# 03_LTC6820.net
KiCad netlist of a schematic drawn in Altium Designer
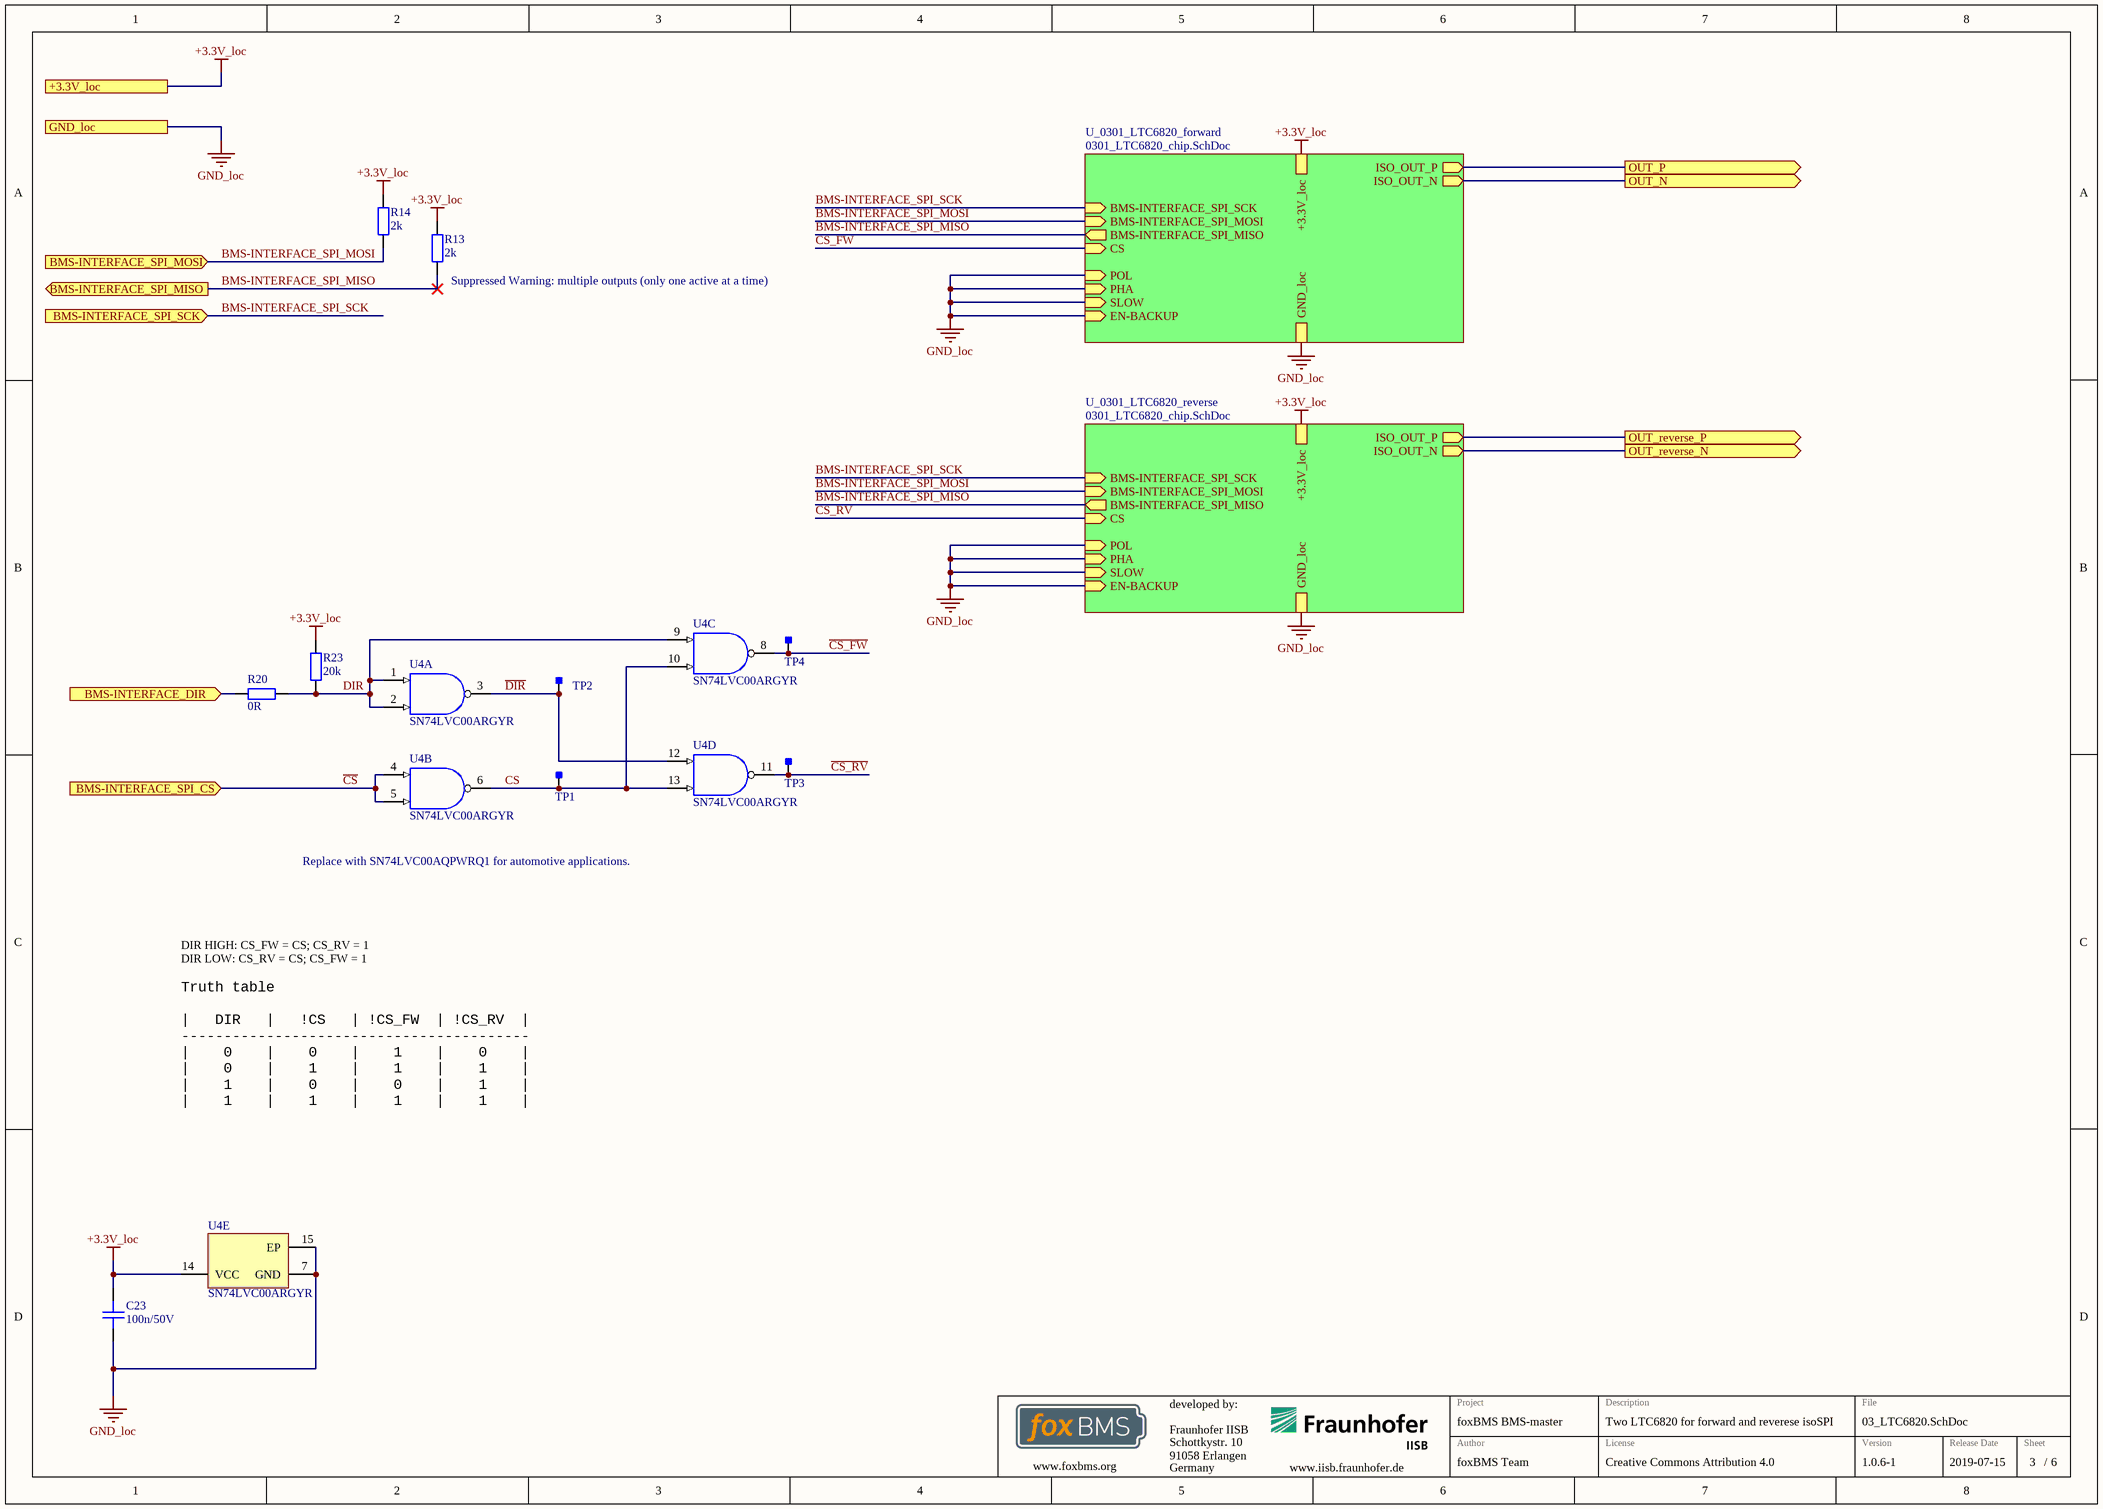
[diagram p0: 03_LTC6820.SchDoc]

(export (version "E")
  (design (tool "Eeschema 10.0.6"))
  (components
    (comp (ref "C23")
      (value "100n/50V")
      (footprint "0603C")
      (description "MLCC")
      (fields (field (name "PART NUMBER") "gen_C_ceramic_100n_50V_X7R_0603"))
      (libsource (lib "master-010106") (part "C"))
    )
    (comp (ref "R13")
      (value "2k")
      (footprint "0603R")
      (description "SMD Resistor 2k 0603")
      (fields (field (name "PART NUMBER") "gen_R_2k_0603") (field (name "TOLERANCE") "1%"))
      (libsource (lib "master-010106") (part "R"))
    )
    (comp (ref "R14")
      (value "2k")
      (footprint "0603R")
      (description "SMD Resistor 2k 0603")
      (fields (field (name "PART NUMBER") "gen_R_2k_0603") (field (name "TOLERANCE") "1%"))
      (libsource (lib "master-010106") (part "R"))
    )
    (comp (ref "R20")
      (value "0R")
      (footprint "0603R")
      (description "SMD Resistor 0R 0603")
      (fields (field (name "PART NUMBER") "gen_R_0R_0603") (field (name "POWER") "0.1W"))
      (libsource (lib "master-010106") (part "R"))
    )
    (comp (ref "R23")
      (value "20k")
      (footprint "0603R")
      (description "SMD Resistor 20k 0603")
      (fields (field (name "PART NUMBER") "gen_R_20k_0603") (field (name "TOLERANCE") "1%"))
      (libsource (lib "master-010106") (part "R"))
    )
    (comp (ref "TP1")
      (value "CS")
      (footprint "Testpoint_S1")
      (description "Testpoint, square")
      (fields (field (name "PART NUMBER") "Testpoint_Square"))
      (libsource (lib "master-010106") (part "Testpoint_Square"))
    )
    (comp (ref "TP2")
      (value "DIR")
      (footprint "Testpoint_S1")
      (description "Testpoint, square")
      (fields (field (name "PART NUMBER") "Testpoint_Square"))
      (libsource (lib "master-010106") (part "Testpoint_Square"))
    )
    (comp (ref "TP3")
      (value "CS_RV")
      (footprint "Testpoint_S1")
      (description "Testpoint, square")
      (fields (field (name "PART NUMBER") "Testpoint_Square"))
      (libsource (lib "master-010106") (part "Testpoint_Square"))
    )
    (comp (ref "TP4")
      (value "CS_FW")
      (footprint "Testpoint_S1")
      (description "Testpoint, square")
      (fields (field (name "PART NUMBER") "Testpoint_Square"))
      (libsource (lib "master-010106") (part "Testpoint_Square"))
    )
    (comp (ref "U4")
      (value "SN74LVC00ARGYR")
      (footprint "RGY0014A_V")
      (description "Quadruple 2-Input Positive-NAND Gate, RGY0014A, LARGE T&R")
      (fields
        (field (name "GENERIC PART NUMBER") "SN74LVC00A")
        (field (name "MANUFACTURER") "Texas Instruments")
      )
      (libsource (lib "Altium Content Vault") (part "TI-SN74LVC00A-RGY0014A-14"))
    )
  )
  (nets
    (net (code "1") (name "+3.3V_loc") (class "Default")
      (node (ref "C23") (pin "2") (pinfunction "2_2") (pintype "passive"))
      (node (ref "R13") (pin "2") (pinfunction "2_2") (pintype "passive"))
      (node (ref "R14") (pin "2") (pinfunction "2_2") (pintype "passive"))
      (node (ref "R23") (pin "2") (pinfunction "2_2") (pintype "passive"))
      (node (ref "U4") (pin "14") (pinfunction "VCC_14") (pintype "power_in"))
    )
    (net (code "2") (name "/BMS-INTERFACE_DIR") (class "Default")
      (node (ref "R20") (pin "1") (pinfunction "1_1") (pintype "passive"))
    )
    (net (code "3") (name "/BMS-INTERFACE_SPI_MISO") (class "Default")
      (node (ref "R13") (pin "1") (pinfunction "1_1") (pintype "passive"))
    )
    (net (code "4") (name "/BMS-INTERFACE_SPI_MOSI") (class "Default")
      (node (ref "R14") (pin "1") (pinfunction "1_1") (pintype "passive"))
    )
    (net (code "6") (name "/CS") (class "Default")
      (node (ref "TP1") (pin "1") (pinfunction "1_1") (pintype "passive"))
      (node (ref "U4") (pin "10") (pinfunction "3B_10") (pintype "input"))
      (node (ref "U4") (pin "13") (pinfunction "4B_13") (pintype "input"))
      (node (ref "U4") (pin "6") (pinfunction "2Y_6") (pintype "open_collector"))
    )
    (net (code "7") (name "/DIR") (class "Default")
      (node (ref "R20") (pin "2") (pinfunction "2_2") (pintype "passive"))
      (node (ref "R23") (pin "1") (pinfunction "1_1") (pintype "passive"))
      (node (ref "U4") (pin "1") (pinfunction "1A_1") (pintype "input"))
      (node (ref "U4") (pin "2") (pinfunction "1B_2") (pintype "input"))
      (node (ref "U4") (pin "9") (pinfunction "3A_9") (pintype "input"))
    )
    (net (code "12") (name "/~{CS_FW}") (class "Default")
      (node (ref "TP4") (pin "1") (pinfunction "1_1") (pintype "passive"))
      (node (ref "U4") (pin "8") (pinfunction "3Y_8") (pintype "open_collector"))
    )
    (net (code "13") (name "/~{CS_RV}") (class "Default")
      (node (ref "TP3") (pin "1") (pinfunction "1_1") (pintype "passive"))
      (node (ref "U4") (pin "11") (pinfunction "4Y_11") (pintype "open_collector"))
    )
    (net (code "14") (name "/~{CS}") (class "Default")
      (node (ref "U4") (pin "4") (pinfunction "2A_4") (pintype "input"))
      (node (ref "U4") (pin "5") (pinfunction "2B_5") (pintype "input"))
    )
    (net (code "15") (name "/~{DIR}") (class "Default")
      (node (ref "TP2") (pin "1") (pinfunction "1_1") (pintype "passive"))
      (node (ref "U4") (pin "12") (pinfunction "4A_12") (pintype "input"))
      (node (ref "U4") (pin "3") (pinfunction "1Y_3") (pintype "open_collector"))
    )
    (net (code "16") (name "GND_loc") (class "Default")
      (node (ref "C23") (pin "1") (pinfunction "1_1") (pintype "passive"))
      (node (ref "U4") (pin "15") (pinfunction "EP_15") (pintype "passive"))
      (node (ref "U4") (pin "7") (pinfunction "GND_7") (pintype "power_in"))
    )
  )
)
